# TK521_Optisk-plugg.net
KiCad netlist of a schematic drawn in Altium Designer
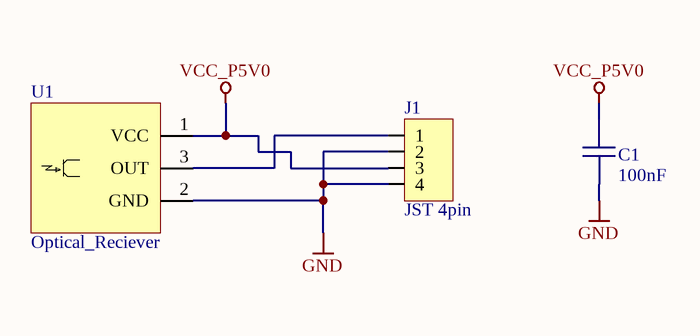
[diagram p0: TK521_Optisk-plugg.SchDoc]

(export (version "E")
  (design (tool "Eeschema 10.0.6"))
  (components
    (comp (ref "C1")
      (value "100nF")
      (footprint "CAPC0603(1608)55_N")
      (description "X7R 50V 5%")
      (libsource (lib "OVLib") (part "CAP"))
    )
    (comp (ref "J1")
      (value "JST 4pin")
      (footprint "JST_4P")
      (description "pris pr. stk.")
      (libsource (lib "OVLib") (part "4PConnector"))
    )
    (comp (ref "U1")
      (value "Optical_Reciever")
      (footprint "TOSLINK_TH")
      (description "TOSLINK Reciever")
      (libsource (lib "OVLib") (part "Optical_Reciever"))
    )
  )
  (nets
    (net (code "1") (name "GND") (class "Default")
      (node (ref "C1") (pin "1") (pinfunction "1_1") (pintype "passive"))
      (node (ref "J1") (pin "2") (pinfunction "2_2") (pintype "passive"))
      (node (ref "J1") (pin "4") (pinfunction "4_4") (pintype "passive"))
      (node (ref "U1") (pin "2") (pinfunction "GND_2") (pintype "passive"))
    )
    (net (code "2") (name "Net-(U1-OUT)") (class "Default")
      (node (ref "J1") (pin "1") (pinfunction "1_1") (pintype "passive"))
      (node (ref "U1") (pin "3") (pinfunction "OUT_3") (pintype "passive"))
    )
    (net (code "3") (name "VCC_P5V0") (class "Default")
      (node (ref "C1") (pin "2") (pinfunction "2_2") (pintype "passive"))
      (node (ref "J1") (pin "3") (pinfunction "3_3") (pintype "passive"))
      (node (ref "U1") (pin "1") (pinfunction "VCC_1") (pintype "passive"))
    )
  )
)
